# debugger-board.net
KiCad netlist of a schematic drawn in EAGLE
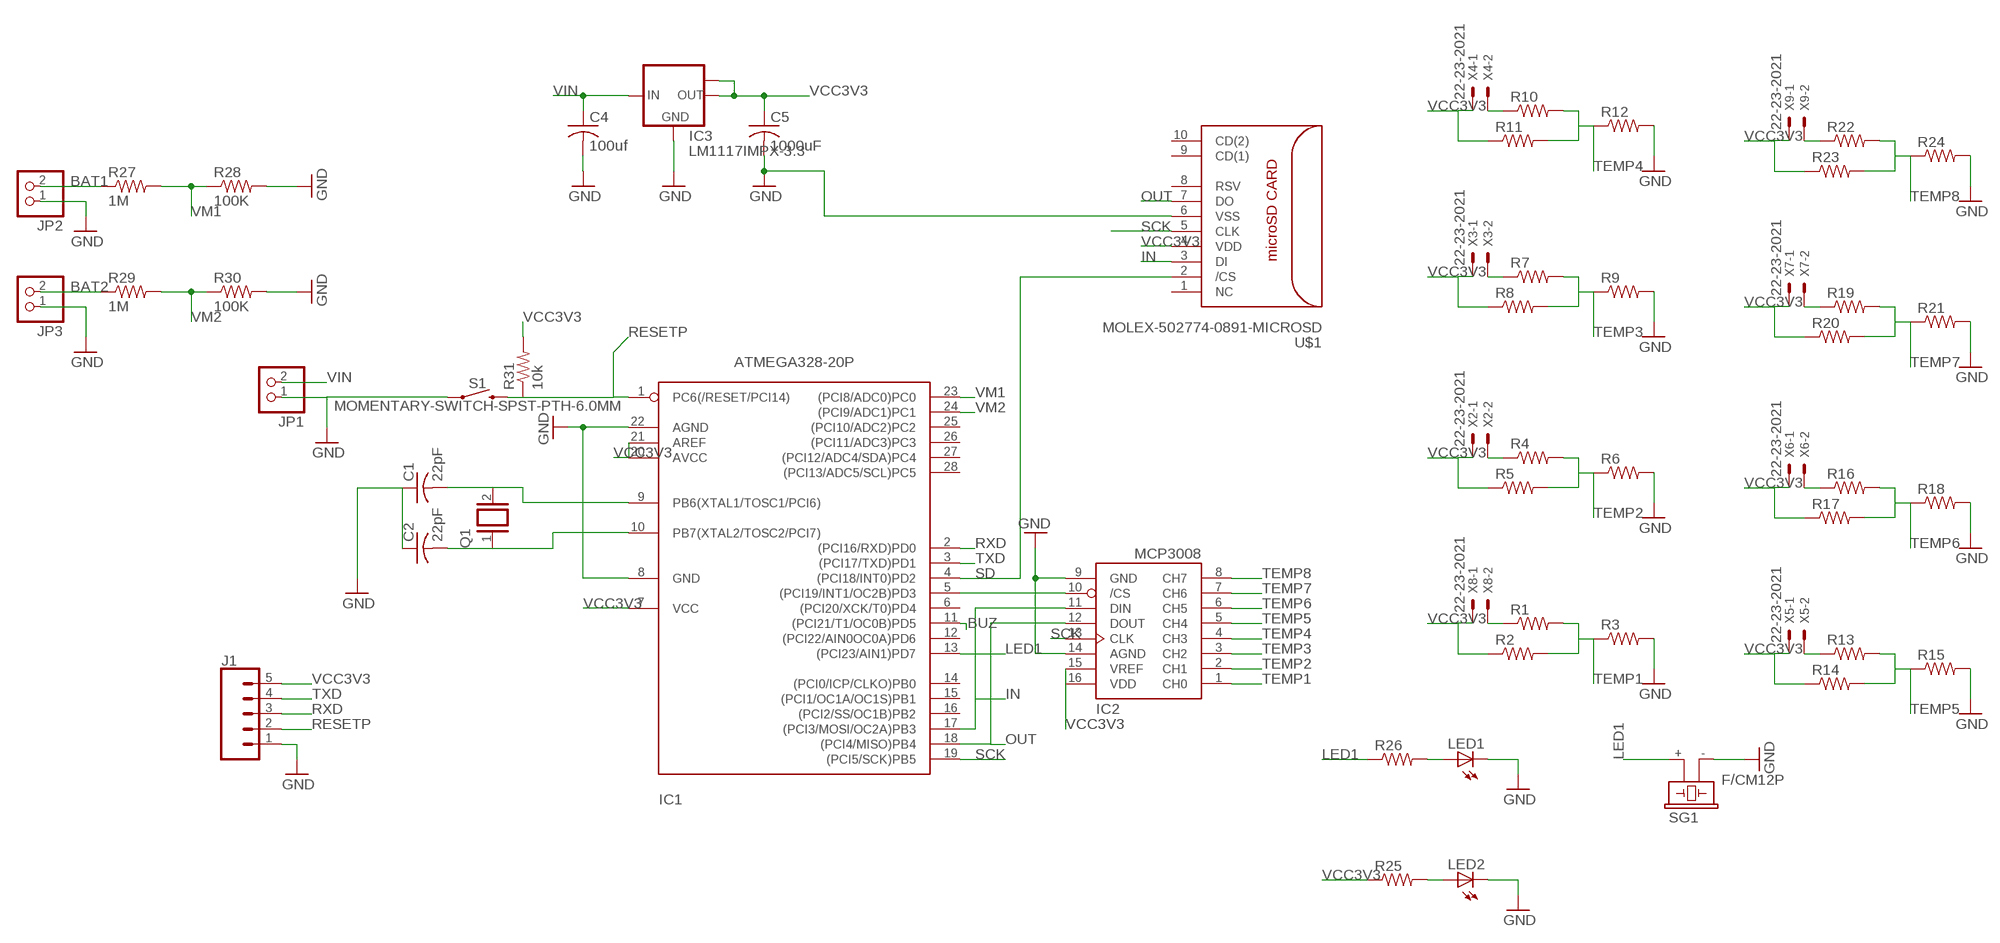
[diagram p0: schematic, sheet 1]

(export (version "E")
  (design (tool "Eeschema 10.0.6"))
  (components
    (comp (ref "C1")
      (value "22pF")
      (footprint "eagle-import:C050-025X075")
      (libsource (lib "eagle-import") (part "C-US050-025X075"))
    )
    (comp (ref "C2")
      (value "22pF")
      (footprint "eagle-import:C050-025X075")
      (libsource (lib "eagle-import") (part "C-US050-025X075"))
    )
    (comp (ref "C4")
      (value "100uf")
      (footprint "eagle-import:C050-025X075")
      (libsource (lib "eagle-import") (part "resistor_C-US050-025X075"))
    )
    (comp (ref "C5")
      (value "1000uF")
      (footprint "eagle-import:C050-025X075")
      (libsource (lib "eagle-import") (part "resistor_C-US050-025X075"))
    )
    (comp (ref "IC1")
      (value "ATMEGA328-20P")
      (footprint "eagle-import:DIL28-3")
      (libsource (lib "eagle-import") (part "ATMEGA328P-20"))
    )
    (comp (ref "IC2")
      (value "MCP3008")
      (footprint "eagle-import:DIL16")
      (libsource (lib "eagle-import") (part "MCP3008"))
    )
    (comp (ref "IC3")
      (value "LM1117IMPX-3.3")
      (footprint "eagle-import:SOT223")
      (libsource (lib "eagle-import") (part "LM1117IMPX-3.3"))
    )
    (comp (ref "J1")
      (value "CONN_05PTH_LONGPADS")
      (footprint "eagle-import:1X05_LONGPADS")
      (libsource (lib "eagle-import") (part "CONN_05PTH_LONGPADS"))
    )
    (comp (ref "JP1")
      (value "PINHD-1X2")
      (footprint "eagle-import:1X02")
      (libsource (lib "eagle-import") (part "PINHD-1X2"))
    )
    (comp (ref "JP2")
      (value "PINHD-1X2")
      (footprint "eagle-import:1X02")
      (libsource (lib "eagle-import") (part "PINHD-1X2"))
    )
    (comp (ref "JP3")
      (value "PINHD-1X2")
      (footprint "eagle-import:1X02")
      (libsource (lib "eagle-import") (part "PINHD-1X2"))
    )
    (comp (ref "LED1")
      (value "LED_ELD260")
      (footprint "eagle-import:LED_LD260")
      (libsource (lib "eagle-import") (part "LED_ELD260"))
    )
    (comp (ref "LED2")
      (value "LED_ELD260")
      (footprint "eagle-import:LED_LD260")
      (libsource (lib "eagle-import") (part "LED_ELD260"))
    )
    (comp (ref "Q1")
      (value "XTAL/S")
      (footprint "eagle-import:QS")
      (libsource (lib "eagle-import") (part "XTAL/S"))
    )
    (comp (ref "R1")
      (value "R-US_0204/5")
      (footprint "eagle-import:0204_5")
      (libsource (lib "eagle-import") (part "R-US_0204/5"))
    )
    (comp (ref "R2")
      (value "R-US_0204/5")
      (footprint "eagle-import:0204_5")
      (libsource (lib "eagle-import") (part "R-US_0204/5"))
    )
    (comp (ref "R3")
      (value "R-US_0204/5")
      (footprint "eagle-import:0204_5")
      (libsource (lib "eagle-import") (part "R-US_0204/5"))
    )
    (comp (ref "R4")
      (value "R-US_0204/5")
      (footprint "eagle-import:0204_5")
      (libsource (lib "eagle-import") (part "R-US_0204/5"))
    )
    (comp (ref "R5")
      (value "R-US_0204/5")
      (footprint "eagle-import:0204_5")
      (libsource (lib "eagle-import") (part "R-US_0204/5"))
    )
    (comp (ref "R6")
      (value "R-US_0204/5")
      (footprint "eagle-import:0204_5")
      (libsource (lib "eagle-import") (part "R-US_0204/5"))
    )
    (comp (ref "R7")
      (value "R-US_0204/5")
      (footprint "eagle-import:0204_5")
      (libsource (lib "eagle-import") (part "R-US_0204/5"))
    )
    (comp (ref "R8")
      (value "R-US_0204/5")
      (footprint "eagle-import:0204_5")
      (libsource (lib "eagle-import") (part "R-US_0204/5"))
    )
    (comp (ref "R9")
      (value "R-US_0204/5")
      (footprint "eagle-import:0204_5")
      (libsource (lib "eagle-import") (part "R-US_0204/5"))
    )
    (comp (ref "R10")
      (value "R-US_0204/5")
      (footprint "eagle-import:0204_5")
      (libsource (lib "eagle-import") (part "R-US_0204/5"))
    )
    (comp (ref "R11")
      (value "R-US_0204/5")
      (footprint "eagle-import:0204_5")
      (libsource (lib "eagle-import") (part "R-US_0204/5"))
    )
    (comp (ref "R12")
      (value "R-US_0204/5")
      (footprint "eagle-import:0204_5")
      (libsource (lib "eagle-import") (part "R-US_0204/5"))
    )
    (comp (ref "R13")
      (value "R-US_0204/5")
      (footprint "eagle-import:0204_5")
      (libsource (lib "eagle-import") (part "R-US_0204/5"))
    )
    (comp (ref "R14")
      (value "R-US_0204/5")
      (footprint "eagle-import:0204_5")
      (libsource (lib "eagle-import") (part "R-US_0204/5"))
    )
    (comp (ref "R15")
      (value "R-US_0204/5")
      (footprint "eagle-import:0204_5")
      (libsource (lib "eagle-import") (part "R-US_0204/5"))
    )
    (comp (ref "R16")
      (value "R-US_0204/5")
      (footprint "eagle-import:0204_5")
      (libsource (lib "eagle-import") (part "R-US_0204/5"))
    )
    (comp (ref "R17")
      (value "R-US_0204/5")
      (footprint "eagle-import:0204_5")
      (libsource (lib "eagle-import") (part "R-US_0204/5"))
    )
    (comp (ref "R18")
      (value "R-US_0204/5")
      (footprint "eagle-import:0204_5")
      (libsource (lib "eagle-import") (part "R-US_0204/5"))
    )
    (comp (ref "R19")
      (value "R-US_0204/5")
      (footprint "eagle-import:0204_5")
      (libsource (lib "eagle-import") (part "R-US_0204/5"))
    )
    (comp (ref "R20")
      (value "R-US_0204/5")
      (footprint "eagle-import:0204_5")
      (libsource (lib "eagle-import") (part "R-US_0204/5"))
    )
    (comp (ref "R21")
      (value "R-US_0204/5")
      (footprint "eagle-import:0204_5")
      (libsource (lib "eagle-import") (part "R-US_0204/5"))
    )
    (comp (ref "R22")
      (value "R-US_0204/5")
      (footprint "eagle-import:0204_5")
      (libsource (lib "eagle-import") (part "R-US_0204/5"))
    )
    (comp (ref "R23")
      (value "R-US_0204/5")
      (footprint "eagle-import:0204_5")
      (libsource (lib "eagle-import") (part "R-US_0204/5"))
    )
    (comp (ref "R24")
      (value "R-US_0204/5")
      (footprint "eagle-import:0204_5")
      (libsource (lib "eagle-import") (part "R-US_0204/5"))
    )
    (comp (ref "R25")
      (value "R-US_0204/5")
      (footprint "eagle-import:0204_5")
      (libsource (lib "eagle-import") (part "R-US_0204/5"))
    )
    (comp (ref "R26")
      (value "R-US_0204/5")
      (footprint "eagle-import:0204_5")
      (libsource (lib "eagle-import") (part "R-US_0204/5"))
    )
    (comp (ref "R27")
      (value "1M")
      (footprint "eagle-import:0204_5")
      (libsource (lib "eagle-import") (part "R-US_0204/5"))
    )
    (comp (ref "R28")
      (value "100K")
      (footprint "eagle-import:0204_5")
      (libsource (lib "eagle-import") (part "R-US_0204/5"))
    )
    (comp (ref "R29")
      (value "1M")
      (footprint "eagle-import:0204_5")
      (libsource (lib "eagle-import") (part "R-US_0204/5"))
    )
    (comp (ref "R30")
      (value "100K")
      (footprint "eagle-import:0204_5")
      (libsource (lib "eagle-import") (part "R-US_0204/5"))
    )
    (comp (ref "R31")
      (value "10k")
      (footprint "eagle-import:0207_7")
      (libsource (lib "eagle-import") (part "resistor_R-US_0207/7"))
    )
    (comp (ref "S1")
      (value "MOMENTARY-SWITCH-SPST-PTH-6.0MM")
      (footprint "eagle-import:TACTILE_SWITCH_PTH_6.0MM")
      (libsource (lib "eagle-import") (part "MOMENTARY-SWITCH-SPST-PTH-6.0MM"))
    )
    (comp (ref "SG1")
      (value "F/CM12P")
      (footprint "eagle-import:F_CM12P")
      (libsource (lib "eagle-import") (part "F/CM12P"))
    )
    (comp (ref "U$1")
      (value "MOLEX-502774-0891-MICROSD")
      (footprint "eagle-import:MOLEX-502774-0891-MICROSD")
      (libsource (lib "eagle-import") (part "MOLEX-502774-0891-MICROSD"))
    )
    (comp (ref "X2")
      (value "22-23-2021")
      (footprint "eagle-import:22-23-2021")
      (fields (field (name "MF") "MOLEX"))
      (libsource (lib "eagle-import") (part "22-23-2021"))
    )
    (comp (ref "X3")
      (value "22-23-2021")
      (footprint "eagle-import:22-23-2021")
      (fields (field (name "MF") "MOLEX"))
      (libsource (lib "eagle-import") (part "22-23-2021"))
    )
    (comp (ref "X4")
      (value "22-23-2021")
      (footprint "eagle-import:22-23-2021")
      (fields (field (name "MF") "MOLEX"))
      (libsource (lib "eagle-import") (part "22-23-2021"))
    )
    (comp (ref "X5")
      (value "22-23-2021")
      (footprint "eagle-import:22-23-2021")
      (fields (field (name "MF") "MOLEX"))
      (libsource (lib "eagle-import") (part "22-23-2021"))
    )
    (comp (ref "X6")
      (value "22-23-2021")
      (footprint "eagle-import:22-23-2021")
      (fields (field (name "MF") "MOLEX"))
      (libsource (lib "eagle-import") (part "22-23-2021"))
    )
    (comp (ref "X7")
      (value "22-23-2021")
      (footprint "eagle-import:22-23-2021")
      (fields (field (name "MF") "MOLEX"))
      (libsource (lib "eagle-import") (part "22-23-2021"))
    )
    (comp (ref "X8")
      (value "22-23-2021")
      (footprint "eagle-import:22-23-2021")
      (fields (field (name "MF") "MOLEX"))
      (libsource (lib "eagle-import") (part "22-23-2021"))
    )
    (comp (ref "X9")
      (value "22-23-2021")
      (footprint "eagle-import:22-23-2021")
      (fields (field (name "MF") "MOLEX"))
      (libsource (lib "eagle-import") (part "22-23-2021"))
    )
  )
  (nets
    (net (code "1") (name "/BAT1") (class "Default")
      (node (ref "JP2") (pin "2") (pinfunction "2_2") (pintype "passive"))
      (node (ref "R27") (pin "1") (pinfunction "1_1") (pintype "passive"))
    )
    (net (code "2") (name "/BAT2") (class "Default")
      (node (ref "JP3") (pin "2") (pinfunction "2_2") (pintype "passive"))
      (node (ref "R29") (pin "1") (pinfunction "1_1") (pintype "passive"))
    )
    (net (code "3") (name "/BUZ") (class "Default")
      (node (ref "IC1") (pin "11") (pinfunction "(PCI21/T1/OC0B)PD5_11") (pintype "bidirectional"))
    )
    (net (code "4") (name "/IN") (class "Default")
      (node (ref "IC1") (pin "17") (pinfunction "(PCI3/MOSI/OC2A)PB3_17") (pintype "bidirectional"))
      (node (ref "IC2") (pin "11") (pinfunction "DIN_11") (pintype "input"))
      (node (ref "U$1") (pin "3") (pinfunction "DI_3") (pintype "bidirectional"))
    )
    (net (code "5") (name "/LED1") (class "Default")
      (node (ref "IC1") (pin "13") (pinfunction "(PCI23/AIN1)PD7_13") (pintype "bidirectional"))
      (node (ref "R26") (pin "1") (pinfunction "1_1") (pintype "passive"))
      (node (ref "SG1") (pin "+") (pinfunction "1_+") (pintype "passive"))
    )
    (net (code "6") (name "/OUT") (class "Default")
      (node (ref "IC1") (pin "18") (pinfunction "(PCI4/MISO)PB4_18") (pintype "bidirectional"))
      (node (ref "IC2") (pin "12") (pinfunction "DOUT_12") (pintype "output"))
      (node (ref "U$1") (pin "7") (pinfunction "DO_7") (pintype "bidirectional"))
    )
    (net (code "7") (name "/RESETP") (class "Default")
      (node (ref "IC1") (pin "1") (pinfunction "PC6(/RESET/PCI14)_1") (pintype "bidirectional"))
      (node (ref "J1") (pin "2") (pinfunction "2_2") (pintype "passive"))
      (node (ref "R31") (pin "1") (pinfunction "1_1") (pintype "passive"))
      (node (ref "S1") (pin "3") (pinfunction "2_3") (pintype "passive"))
    )
    (net (code "8") (name "/RXD") (class "Default")
      (node (ref "IC1") (pin "2") (pinfunction "(PCI16/RXD)PD0_2") (pintype "bidirectional"))
      (node (ref "J1") (pin "3") (pinfunction "3_3") (pintype "passive"))
    )
    (net (code "9") (name "/SCK") (class "Default")
      (node (ref "IC1") (pin "19") (pinfunction "(PCI5/SCK)PB5_19") (pintype "bidirectional"))
      (node (ref "IC2") (pin "13") (pinfunction "CLK_13") (pintype "input"))
      (node (ref "U$1") (pin "5") (pinfunction "CLK_5") (pintype "bidirectional"))
    )
    (net (code "10") (name "/SD") (class "Default")
      (node (ref "IC1") (pin "4") (pinfunction "(PCI18/INT0)PD2_4") (pintype "bidirectional"))
      (node (ref "U$1") (pin "2") (pinfunction "/CS_2") (pintype "bidirectional"))
    )
    (net (code "11") (name "/TEMP1") (class "Default")
      (node (ref "IC2") (pin "1") (pinfunction "CH0_1") (pintype "input"))
      (node (ref "R1") (pin "2") (pinfunction "2_2") (pintype "passive"))
      (node (ref "R2") (pin "2") (pinfunction "2_2") (pintype "passive"))
      (node (ref "R3") (pin "1") (pinfunction "1_1") (pintype "passive"))
    )
    (net (code "12") (name "/TEMP2") (class "Default")
      (node (ref "IC2") (pin "2") (pinfunction "CH1_2") (pintype "input"))
      (node (ref "R4") (pin "2") (pinfunction "2_2") (pintype "passive"))
      (node (ref "R5") (pin "2") (pinfunction "2_2") (pintype "passive"))
      (node (ref "R6") (pin "1") (pinfunction "1_1") (pintype "passive"))
    )
    (net (code "13") (name "/TEMP3") (class "Default")
      (node (ref "IC2") (pin "3") (pinfunction "CH2_3") (pintype "input"))
      (node (ref "R7") (pin "2") (pinfunction "2_2") (pintype "passive"))
      (node (ref "R8") (pin "2") (pinfunction "2_2") (pintype "passive"))
      (node (ref "R9") (pin "1") (pinfunction "1_1") (pintype "passive"))
    )
    (net (code "14") (name "/TEMP4") (class "Default")
      (node (ref "IC2") (pin "4") (pinfunction "CH3_4") (pintype "input"))
      (node (ref "R10") (pin "2") (pinfunction "2_2") (pintype "passive"))
      (node (ref "R11") (pin "2") (pinfunction "2_2") (pintype "passive"))
      (node (ref "R12") (pin "1") (pinfunction "1_1") (pintype "passive"))
    )
    (net (code "15") (name "/TEMP5") (class "Default")
      (node (ref "IC2") (pin "5") (pinfunction "CH4_5") (pintype "input"))
      (node (ref "R13") (pin "2") (pinfunction "2_2") (pintype "passive"))
      (node (ref "R14") (pin "2") (pinfunction "2_2") (pintype "passive"))
      (node (ref "R15") (pin "1") (pinfunction "1_1") (pintype "passive"))
    )
    (net (code "16") (name "/TEMP6") (class "Default")
      (node (ref "IC2") (pin "6") (pinfunction "CH5_6") (pintype "input"))
      (node (ref "R16") (pin "2") (pinfunction "2_2") (pintype "passive"))
      (node (ref "R17") (pin "2") (pinfunction "2_2") (pintype "passive"))
      (node (ref "R18") (pin "1") (pinfunction "1_1") (pintype "passive"))
    )
    (net (code "17") (name "/TEMP7") (class "Default")
      (node (ref "IC2") (pin "7") (pinfunction "CH6_7") (pintype "input"))
      (node (ref "R19") (pin "2") (pinfunction "2_2") (pintype "passive"))
      (node (ref "R20") (pin "2") (pinfunction "2_2") (pintype "passive"))
      (node (ref "R21") (pin "1") (pinfunction "1_1") (pintype "passive"))
    )
    (net (code "18") (name "/TEMP8") (class "Default")
      (node (ref "IC2") (pin "8") (pinfunction "CH7_8") (pintype "input"))
      (node (ref "R22") (pin "2") (pinfunction "2_2") (pintype "passive"))
      (node (ref "R23") (pin "2") (pinfunction "2_2") (pintype "passive"))
      (node (ref "R24") (pin "1") (pinfunction "1_1") (pintype "passive"))
    )
    (net (code "19") (name "/TXD") (class "Default")
      (node (ref "IC1") (pin "3") (pinfunction "(PCI17/TXD)PD1_3") (pintype "bidirectional"))
      (node (ref "J1") (pin "4") (pinfunction "4_4") (pintype "passive"))
    )
    (net (code "20") (name "/VCC3V3") (class "Default")
      (node (ref "C5") (pin "1") (pinfunction "1_1") (pintype "passive"))
      (node (ref "IC1") (pin "20") (pinfunction "AVCC_20") (pintype "bidirectional"))
      (node (ref "IC1") (pin "21") (pinfunction "AREF_21") (pintype "bidirectional"))
      (node (ref "IC1") (pin "7") (pinfunction "VCC_7") (pintype "bidirectional"))
      (node (ref "IC2") (pin "15") (pinfunction "VREF_15") (pintype "input"))
      (node (ref "IC2") (pin "16") (pinfunction "VDD_16") (pintype "power_in"))
      (node (ref "IC3") (pin "2") (pinfunction "OUT_2") (pintype "passive"))
      (node (ref "IC3") (pin "TAB") (pinfunction "OUT1_TAB") (pintype "passive"))
      (node (ref "J1") (pin "5") (pinfunction "5_5") (pintype "passive"))
      (node (ref "R11") (pin "1") (pinfunction "1_1") (pintype "passive"))
      (node (ref "R14") (pin "1") (pinfunction "1_1") (pintype "passive"))
      (node (ref "R17") (pin "1") (pinfunction "1_1") (pintype "passive"))
      (node (ref "R2") (pin "1") (pinfunction "1_1") (pintype "passive"))
      (node (ref "R20") (pin "1") (pinfunction "1_1") (pintype "passive"))
      (node (ref "R23") (pin "1") (pinfunction "1_1") (pintype "passive"))
      (node (ref "R25") (pin "1") (pinfunction "1_1") (pintype "passive"))
      (node (ref "R31") (pin "2") (pinfunction "2_2") (pintype "passive"))
      (node (ref "R5") (pin "1") (pinfunction "1_1") (pintype "passive"))
      (node (ref "R8") (pin "1") (pinfunction "1_1") (pintype "passive"))
      (node (ref "U$1") (pin "4") (pinfunction "VDD_4") (pintype "bidirectional"))
      (node (ref "X2") (pin "1") (pinfunction "S_1") (pintype "passive"))
      (node (ref "X3") (pin "1") (pinfunction "S_1") (pintype "passive"))
      (node (ref "X4") (pin "1") (pinfunction "S_1") (pintype "passive"))
      (node (ref "X5") (pin "1") (pinfunction "S_1") (pintype "passive"))
      (node (ref "X6") (pin "1") (pinfunction "S_1") (pintype "passive"))
      (node (ref "X7") (pin "1") (pinfunction "S_1") (pintype "passive"))
      (node (ref "X8") (pin "1") (pinfunction "S_1") (pintype "passive"))
      (node (ref "X9") (pin "1") (pinfunction "S_1") (pintype "passive"))
    )
    (net (code "21") (name "/VIN") (class "Default")
      (node (ref "C4") (pin "1") (pinfunction "1_1") (pintype "passive"))
      (node (ref "IC3") (pin "3") (pinfunction "IN_3") (pintype "input"))
      (node (ref "JP1") (pin "2") (pinfunction "2_2") (pintype "passive"))
    )
    (net (code "22") (name "/VM1") (class "Default")
      (node (ref "IC1") (pin "23") (pinfunction "(PCI8/ADC0)PC0_23") (pintype "bidirectional"))
      (node (ref "R27") (pin "2") (pinfunction "2_2") (pintype "passive"))
      (node (ref "R28") (pin "1") (pinfunction "1_1") (pintype "passive"))
    )
    (net (code "23") (name "/VM2") (class "Default")
      (node (ref "IC1") (pin "24") (pinfunction "(PCI9/ADC1)PC1_24") (pintype "bidirectional"))
      (node (ref "R29") (pin "2") (pinfunction "2_2") (pintype "passive"))
      (node (ref "R30") (pin "1") (pinfunction "1_1") (pintype "passive"))
    )
    (net (code "24") (name "GND") (class "Default")
      (node (ref "C1") (pin "1") (pinfunction "1_1") (pintype "passive"))
      (node (ref "C2") (pin "1") (pinfunction "1_1") (pintype "passive"))
      (node (ref "C4") (pin "2") (pinfunction "2_2") (pintype "passive"))
      (node (ref "C5") (pin "2") (pinfunction "2_2") (pintype "passive"))
      (node (ref "IC1") (pin "22") (pinfunction "AGND_22") (pintype "bidirectional"))
      (node (ref "IC1") (pin "8") (pinfunction "GND_8") (pintype "bidirectional"))
      (node (ref "IC2") (pin "14") (pinfunction "AGND_14") (pintype "power_in"))
      (node (ref "IC2") (pin "9") (pinfunction "GND_9") (pintype "power_in"))
      (node (ref "IC3") (pin "1") (pinfunction "GND_1") (pintype "input"))
      (node (ref "J1") (pin "1") (pinfunction "1_1") (pintype "passive"))
      (node (ref "JP1") (pin "1") (pinfunction "1_1") (pintype "passive"))
      (node (ref "JP2") (pin "1") (pinfunction "1_1") (pintype "passive"))
      (node (ref "JP3") (pin "1") (pinfunction "1_1") (pintype "passive"))
      (node (ref "LED1") (pin "K") (pinfunction "C_K") (pintype "passive"))
      (node (ref "LED2") (pin "K") (pinfunction "C_K") (pintype "passive"))
      (node (ref "R12") (pin "2") (pinfunction "2_2") (pintype "passive"))
      (node (ref "R15") (pin "2") (pinfunction "2_2") (pintype "passive"))
      (node (ref "R18") (pin "2") (pinfunction "2_2") (pintype "passive"))
      (node (ref "R21") (pin "2") (pinfunction "2_2") (pintype "passive"))
      (node (ref "R24") (pin "2") (pinfunction "2_2") (pintype "passive"))
      (node (ref "R28") (pin "2") (pinfunction "2_2") (pintype "passive"))
      (node (ref "R3") (pin "2") (pinfunction "2_2") (pintype "passive"))
      (node (ref "R30") (pin "2") (pinfunction "2_2") (pintype "passive"))
      (node (ref "R6") (pin "2") (pinfunction "2_2") (pintype "passive"))
      (node (ref "R9") (pin "2") (pinfunction "2_2") (pintype "passive"))
      (node (ref "S1") (pin "1") (pinfunction "1_1") (pintype "passive"))
      (node (ref "SG1") (pin "-") (pinfunction "2_-") (pintype "passive"))
      (node (ref "U$1") (pin "6") (pinfunction "VSS_6") (pintype "bidirectional"))
    )
    (net (code "25") (name "Net-(IC1-(PCI19{slash}INT1{slash}OC2B)PD3)") (class "Default")
      (node (ref "IC1") (pin "5") (pinfunction "(PCI19/INT1/OC2B)PD3_5") (pintype "bidirectional"))
      (node (ref "IC2") (pin "10") (pinfunction "/CS_10") (pintype "input"))
    )
    (net (code "26") (name "Net-(IC1-PB6(XTAL1{slash}TOSC1{slash}PCI6))") (class "Default")
      (node (ref "C1") (pin "2") (pinfunction "2_2") (pintype "passive"))
      (node (ref "IC1") (pin "9") (pinfunction "PB6(XTAL1/TOSC1/PCI6)_9") (pintype "bidirectional"))
      (node (ref "Q1") (pin "2") (pinfunction "2_2") (pintype "passive"))
    )
    (net (code "27") (name "Net-(IC1-PB7(XTAL2{slash}TOSC2{slash}PCI7))") (class "Default")
      (node (ref "C2") (pin "2") (pinfunction "2_2") (pintype "passive"))
      (node (ref "IC1") (pin "10") (pinfunction "PB7(XTAL2/TOSC2/PCI7)_10") (pintype "bidirectional"))
      (node (ref "Q1") (pin "1") (pinfunction "1_1") (pintype "passive"))
    )
    (net (code "28") (name "Net-(LED1-PadA)") (class "Default")
      (node (ref "LED1") (pin "A") (pinfunction "A_A") (pintype "passive"))
      (node (ref "R26") (pin "2") (pinfunction "2_2") (pintype "passive"))
    )
    (net (code "29") (name "Net-(LED2-PadA)") (class "Default")
      (node (ref "LED2") (pin "A") (pinfunction "A_A") (pintype "passive"))
      (node (ref "R25") (pin "2") (pinfunction "2_2") (pintype "passive"))
    )
    (net (code "30") (name "Net-(X2B-S)") (class "Default")
      (node (ref "R4") (pin "1") (pinfunction "1_1") (pintype "passive"))
      (node (ref "X2") (pin "2") (pinfunction "S_2") (pintype "passive"))
    )
    (net (code "31") (name "Net-(X3B-S)") (class "Default")
      (node (ref "R7") (pin "1") (pinfunction "1_1") (pintype "passive"))
      (node (ref "X3") (pin "2") (pinfunction "S_2") (pintype "passive"))
    )
    (net (code "32") (name "Net-(X4B-S)") (class "Default")
      (node (ref "R10") (pin "1") (pinfunction "1_1") (pintype "passive"))
      (node (ref "X4") (pin "2") (pinfunction "S_2") (pintype "passive"))
    )
    (net (code "33") (name "Net-(X5B-S)") (class "Default")
      (node (ref "R13") (pin "1") (pinfunction "1_1") (pintype "passive"))
      (node (ref "X5") (pin "2") (pinfunction "S_2") (pintype "passive"))
    )
    (net (code "34") (name "Net-(X6B-S)") (class "Default")
      (node (ref "R16") (pin "1") (pinfunction "1_1") (pintype "passive"))
      (node (ref "X6") (pin "2") (pinfunction "S_2") (pintype "passive"))
    )
    (net (code "35") (name "Net-(X7B-S)") (class "Default")
      (node (ref "R19") (pin "1") (pinfunction "1_1") (pintype "passive"))
      (node (ref "X7") (pin "2") (pinfunction "S_2") (pintype "passive"))
    )
    (net (code "36") (name "Net-(X8B-S)") (class "Default")
      (node (ref "R1") (pin "1") (pinfunction "1_1") (pintype "passive"))
      (node (ref "X8") (pin "2") (pinfunction "S_2") (pintype "passive"))
    )
    (net (code "37") (name "Net-(X9B-S)") (class "Default")
      (node (ref "R22") (pin "1") (pinfunction "1_1") (pintype "passive"))
      (node (ref "X9") (pin "2") (pinfunction "S_2") (pintype "passive"))
    )
    (net (code "38") (name "unconnected-(IC1-(PCI0{slash}ICP{slash}CLKO)PB0-Pad14)") (class "Default")
      (node (ref "IC1") (pin "14") (pinfunction "(PCI0/ICP/CLKO)PB0_14") (pintype "bidirectional"))
    )
    (net (code "39") (name "unconnected-(IC1-(PCI1{slash}OC1A{slash}OC1S)PB1-Pad15)") (class "Default")
      (node (ref "IC1") (pin "15") (pinfunction "(PCI1/OC1A/OC1S)PB1_15") (pintype "bidirectional"))
    )
    (net (code "40") (name "unconnected-(IC1-(PCI2{slash}SS{slash}OC1B)PB2-Pad16)") (class "Default")
      (node (ref "IC1") (pin "16") (pinfunction "(PCI2/SS/OC1B)PB2_16") (pintype "bidirectional"))
    )
    (net (code "41") (name "unconnected-(IC1-(PCI10{slash}ADC2)PC2-Pad25)") (class "Default")
      (node (ref "IC1") (pin "25") (pinfunction "(PCI10/ADC2)PC2_25") (pintype "bidirectional"))
    )
    (net (code "42") (name "unconnected-(IC1-(PCI11{slash}ADC3)PC3-Pad26)") (class "Default")
      (node (ref "IC1") (pin "26") (pinfunction "(PCI11/ADC3)PC3_26") (pintype "bidirectional"))
    )
    (net (code "43") (name "unconnected-(IC1-(PCI12{slash}ADC4{slash}SDA)PC4-Pad27)") (class "Default")
      (node (ref "IC1") (pin "27") (pinfunction "(PCI12/ADC4/SDA)PC4_27") (pintype "bidirectional"))
    )
    (net (code "44") (name "unconnected-(IC1-(PCI13{slash}ADC5{slash}SCL)PC5-Pad28)") (class "Default")
      (node (ref "IC1") (pin "28") (pinfunction "(PCI13/ADC5/SCL)PC5_28") (pintype "bidirectional"))
    )
    (net (code "45") (name "unconnected-(IC1-(PCI20{slash}XCK{slash}T0)PD4-Pad6)") (class "Default")
      (node (ref "IC1") (pin "6") (pinfunction "(PCI20/XCK/T0)PD4_6") (pintype "bidirectional"))
    )
    (net (code "46") (name "unconnected-(IC1-(PCI22{slash}AIN0OC0A)PD6-Pad12)") (class "Default")
      (node (ref "IC1") (pin "12") (pinfunction "(PCI22/AIN0OC0A)PD6_12") (pintype "bidirectional"))
    )
    (net (code "47") (name "unconnected-(U$1-CD(1)-Pad9)") (class "Default")
      (node (ref "U$1") (pin "9") (pinfunction "CD(1)_9") (pintype "bidirectional"))
    )
    (net (code "48") (name "unconnected-(U$1-CD(2)-Pad10)") (class "Default")
      (node (ref "U$1") (pin "10") (pinfunction "CD(2)_10") (pintype "bidirectional"))
    )
    (net (code "49") (name "unconnected-(U$1-NC-Pad1)") (class "Default")
      (node (ref "U$1") (pin "1") (pinfunction "NC_1") (pintype "bidirectional"))
    )
    (net (code "50") (name "unconnected-(U$1-RSV-Pad8)") (class "Default")
      (node (ref "U$1") (pin "8") (pinfunction "RSV_8") (pintype "bidirectional"))
    )
  )
)
